# top.net
KiCad netlist of a schematic drawn in Altium Designer
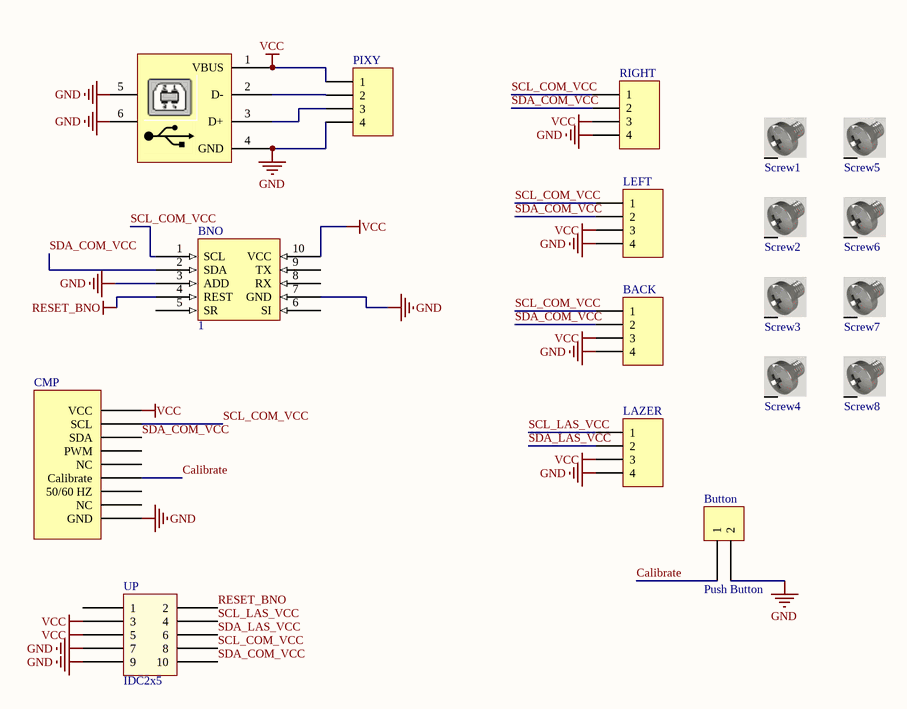
[diagram p0: top.SchDoc]

(export (version "E")
  (design (tool "Eeschema 10.0.6"))
  (components
    (comp (ref "BACK")
      (value "LEFT")
      (footprint "HDR1X4")
      (description "Header, 4-Pin")
      (fields (field (name "PUBLISHER") "Altium Limited"))
      (libsource (lib "Miscellaneous Connectors") (part "Header 4"))
    )
    (comp (ref "BNO") (value "1") (footprint "DIP10") (libsource (lib "Farz1") (part "Gy955")))
    (comp (ref "Button")
      (value "Push Button")
      (footprint "Push Button")
      (libsource (lib "Farz1") (part "Push Button"))
    )
    (comp (ref "CMP") (value "CMP03") (footprint "CMP03") (libsource (lib "Farz1") (part "CMP03")))
    (comp (ref "LAZER")
      (value "LEFT")
      (footprint "HDR1X4")
      (description "Header, 4-Pin")
      (fields (field (name "PUBLISHER") "Altium Limited"))
      (libsource (lib "Miscellaneous Connectors") (part "Header 4"))
    )
    (comp (ref "LEFT")
      (value "LEFT")
      (footprint "HDR1X4")
      (description "Header, 4-Pin")
      (fields (field (name "PUBLISHER") "Altium Limited"))
      (libsource (lib "Miscellaneous Connectors") (part "Header 4"))
    )
    (comp (ref "PIXY")
      (value "Header 4")
      (footprint "HDR1X4")
      (description "Header, 4-Pin")
      (fields (field (name "PUBLISHER") "Altium Limited"))
      (libsource (lib "Miscellaneous Connectors") (part "Header 4"))
    )
    (comp (ref "RIGHT")
      (value "LEFT")
      (footprint "HDR1X4")
      (description "Header, 4-Pin")
      (fields (field (name "PUBLISHER") "Altium Limited"))
      (libsource (lib "Miscellaneous Connectors") (part "Header 4"))
    )
    (comp (ref "Screw1")
      (value "Screw")
      (footprint "Screw")
      (fields (field (name "PUBLISHER") "Altium Limited"))
      (libsource (lib "Farzanegan") (part "Screw"))
    )
    (comp (ref "Screw2")
      (value "Screw")
      (footprint "Screw")
      (fields (field (name "PUBLISHER") "Altium Limited"))
      (libsource (lib "Farzanegan") (part "Screw"))
    )
    (comp (ref "Screw3")
      (value "Screw")
      (footprint "Screw")
      (fields (field (name "PUBLISHER") "Altium Limited"))
      (libsource (lib "Farzanegan") (part "Screw"))
    )
    (comp (ref "Screw4")
      (value "Screw")
      (footprint "Screw")
      (fields (field (name "PUBLISHER") "Altium Limited"))
      (libsource (lib "Farzanegan") (part "Screw"))
    )
    (comp (ref "Screw5")
      (value "Screw")
      (footprint "Screw")
      (fields (field (name "PUBLISHER") "Altium Limited"))
      (libsource (lib "Farzanegan") (part "Screw"))
    )
    (comp (ref "Screw6")
      (value "Screw")
      (footprint "Screw")
      (fields (field (name "PUBLISHER") "Altium Limited"))
      (libsource (lib "Farzanegan") (part "Screw"))
    )
    (comp (ref "Screw7")
      (value "Screw")
      (footprint "Screw")
      (fields (field (name "PUBLISHER") "Altium Limited"))
      (libsource (lib "Farzanegan") (part "Screw"))
    )
    (comp (ref "Screw8")
      (value "Screw")
      (footprint "Screw")
      (fields (field (name "PUBLISHER") "Altium Limited"))
      (libsource (lib "Farzanegan") (part "Screw"))
    )
    (comp (ref "UP") (value "IDC2x5") (footprint "IDC 2x5") (libsource (lib "Farz1") (part "IDC 2x5")))
    (comp (ref "USB_B")
      (value "USB_B")
      (footprint "USB_B.1")
      (description "USB B")
      (fields (field (name "PUBLISHER") "Altium Limited"))
      (libsource (lib "Farz1") (part "USB_B"))
    )
  )
  (nets
    (net (code "1") (name "/Calibrate") (class "Default")
      (node (ref "Button") (pin "1") (pinfunction "1_1") (pintype "passive"))
      (node (ref "CMP") (pin "6") (pinfunction "Calibrate_6") (pintype "passive"))
    )
    (net (code "2") (name "/SCL_COM_VCC") (class "Default")
      (node (ref "BACK") (pin "1") (pinfunction "1_1") (pintype "passive"))
      (node (ref "BNO") (pin "1") (pinfunction "SCL_1") (pintype "input"))
      (node (ref "CMP") (pin "2") (pinfunction "SCL_2") (pintype "passive"))
      (node (ref "LEFT") (pin "1") (pinfunction "1_1") (pintype "passive"))
      (node (ref "RIGHT") (pin "1") (pinfunction "1_1") (pintype "passive"))
      (node (ref "UP") (pin "8") (pinfunction "8_8") (pintype "passive"))
    )
    (net (code "3") (name "/SCL_LAS_VCC") (class "Default")
      (node (ref "LAZER") (pin "1") (pinfunction "1_1") (pintype "passive"))
      (node (ref "UP") (pin "4") (pinfunction "4_4") (pintype "passive"))
    )
    (net (code "4") (name "/SDA_COM_VCC") (class "Default")
      (node (ref "BACK") (pin "2") (pinfunction "2_2") (pintype "passive"))
      (node (ref "BNO") (pin "2") (pinfunction "SDA_2") (pintype "input"))
      (node (ref "CMP") (pin "3") (pinfunction "SDA_3") (pintype "passive"))
      (node (ref "LEFT") (pin "2") (pinfunction "2_2") (pintype "passive"))
      (node (ref "RIGHT") (pin "2") (pinfunction "2_2") (pintype "passive"))
      (node (ref "UP") (pin "10") (pinfunction "10_10") (pintype "passive"))
    )
    (net (code "5") (name "/SDA_LAS_VCC") (class "Default")
      (node (ref "LAZER") (pin "2") (pinfunction "2_2") (pintype "passive"))
      (node (ref "UP") (pin "6") (pinfunction "6_6") (pintype "passive"))
    )
    (net (code "6") (name "GND") (class "Default")
      (node (ref "BACK") (pin "4") (pinfunction "4_4") (pintype "passive"))
      (node (ref "BNO") (pin "3") (pinfunction "ADD_3") (pintype "input"))
      (node (ref "BNO") (pin "7") (pinfunction "GND_7") (pintype "input"))
      (node (ref "Button") (pin "2") (pinfunction "2_2") (pintype "passive"))
      (node (ref "CMP") (pin "9") (pinfunction "GND_9") (pintype "passive"))
      (node (ref "LAZER") (pin "4") (pinfunction "4_4") (pintype "passive"))
      (node (ref "LEFT") (pin "4") (pinfunction "4_4") (pintype "passive"))
      (node (ref "PIXY") (pin "4") (pinfunction "4_4") (pintype "passive"))
      (node (ref "RIGHT") (pin "4") (pinfunction "4_4") (pintype "passive"))
      (node (ref "UP") (pin "7") (pinfunction "7_7") (pintype "passive"))
      (node (ref "UP") (pin "9") (pinfunction "9_9") (pintype "passive"))
      (node (ref "USB_B") (pin "4") (pinfunction "GND_4") (pintype "power_in"))
      (node (ref "USB_B") (pin "5") (pinfunction "5_5") (pintype "passive"))
      (node (ref "USB_B") (pin "6") (pinfunction "6_6") (pintype "passive"))
    )
    (net (code "7") (name "Net-(USB_B-D+)") (class "Default")
      (node (ref "PIXY") (pin "3") (pinfunction "3_3") (pintype "passive"))
      (node (ref "USB_B") (pin "3") (pinfunction "D+_3") (pintype "passive"))
    )
    (net (code "8") (name "Net-(USB_B-D-)") (class "Default")
      (node (ref "PIXY") (pin "2") (pinfunction "2_2") (pintype "passive"))
      (node (ref "USB_B") (pin "2") (pinfunction "D-_2") (pintype "passive"))
    )
    (net (code "9") (name "RESET_BNO") (class "Default")
      (node (ref "BNO") (pin "4") (pinfunction "REST_4") (pintype "input"))
      (node (ref "UP") (pin "2") (pinfunction "2_2") (pintype "passive"))
    )
    (net (code "10") (name "VCC") (class "Default")
      (node (ref "BACK") (pin "3") (pinfunction "3_3") (pintype "passive"))
      (node (ref "BNO") (pin "10") (pinfunction "VCC_10") (pintype "input"))
      (node (ref "CMP") (pin "1") (pinfunction "VCC_1") (pintype "passive"))
      (node (ref "LAZER") (pin "3") (pinfunction "3_3") (pintype "passive"))
      (node (ref "LEFT") (pin "3") (pinfunction "3_3") (pintype "passive"))
      (node (ref "PIXY") (pin "1") (pinfunction "1_1") (pintype "passive"))
      (node (ref "RIGHT") (pin "3") (pinfunction "3_3") (pintype "passive"))
      (node (ref "UP") (pin "3") (pinfunction "3_3") (pintype "passive"))
      (node (ref "UP") (pin "5") (pinfunction "5_5") (pintype "passive"))
      (node (ref "USB_B") (pin "1") (pinfunction "VBUS_1") (pintype "power_in"))
    )
    (net (code "11") (name "unconnected-(BNO-RX-Pad8)") (class "Default")
      (node (ref "BNO") (pin "8") (pinfunction "RX_8") (pintype "input"))
    )
    (net (code "12") (name "unconnected-(BNO-SI-Pad6)") (class "Default")
      (node (ref "BNO") (pin "6") (pinfunction "SI_6") (pintype "input"))
    )
    (net (code "13") (name "unconnected-(BNO-SR-Pad5)") (class "Default")
      (node (ref "BNO") (pin "5") (pinfunction "SR_5") (pintype "input"))
    )
    (net (code "14") (name "unconnected-(BNO-TX-Pad9)") (class "Default")
      (node (ref "BNO") (pin "9") (pinfunction "TX_9") (pintype "input"))
    )
    (net (code "15") (name "unconnected-(CMP-50{slash}60_HZ-Pad7)") (class "Default")
      (node (ref "CMP") (pin "7") (pinfunction "50/60_HZ_7") (pintype "passive"))
    )
    (net (code "16") (name "unconnected-(CMP-NC-Pad5)") (class "Default")
      (node (ref "CMP") (pin "5") (pinfunction "NC_5") (pintype "passive"))
    )
    (net (code "17") (name "unconnected-(CMP-NC-Pad8)") (class "Default")
      (node (ref "CMP") (pin "8") (pinfunction "NC_8") (pintype "passive"))
    )
    (net (code "18") (name "unconnected-(CMP-PWM-Pad4)") (class "Default")
      (node (ref "CMP") (pin "4") (pinfunction "PWM_4") (pintype "passive"))
    )
    (net (code "19") (name "unconnected-(Screw1-PadS)") (class "Default")
      (node (ref "Screw1") (pin "S") (pinfunction "S_S") (pintype "passive"))
    )
    (net (code "20") (name "unconnected-(Screw2-PadS)") (class "Default")
      (node (ref "Screw2") (pin "S") (pinfunction "S_S") (pintype "passive"))
    )
    (net (code "21") (name "unconnected-(Screw3-PadS)") (class "Default")
      (node (ref "Screw3") (pin "S") (pinfunction "S_S") (pintype "passive"))
    )
    (net (code "22") (name "unconnected-(Screw4-PadS)") (class "Default")
      (node (ref "Screw4") (pin "S") (pinfunction "S_S") (pintype "passive"))
    )
    (net (code "23") (name "unconnected-(Screw5-PadS)") (class "Default")
      (node (ref "Screw5") (pin "S") (pinfunction "S_S") (pintype "passive"))
    )
    (net (code "24") (name "unconnected-(Screw6-PadS)") (class "Default")
      (node (ref "Screw6") (pin "S") (pinfunction "S_S") (pintype "passive"))
    )
    (net (code "25") (name "unconnected-(Screw7-PadS)") (class "Default")
      (node (ref "Screw7") (pin "S") (pinfunction "S_S") (pintype "passive"))
    )
    (net (code "26") (name "unconnected-(Screw8-PadS)") (class "Default")
      (node (ref "Screw8") (pin "S") (pinfunction "S_S") (pintype "passive"))
    )
    (net (code "27") (name "unconnected-(UP-Pad1)") (class "Default")
      (node (ref "UP") (pin "1") (pinfunction "1_1") (pintype "passive"))
    )
  )
)
